# USB_CY7C68001-56LFC.net
KiCad netlist of a schematic drawn in Altium Designer
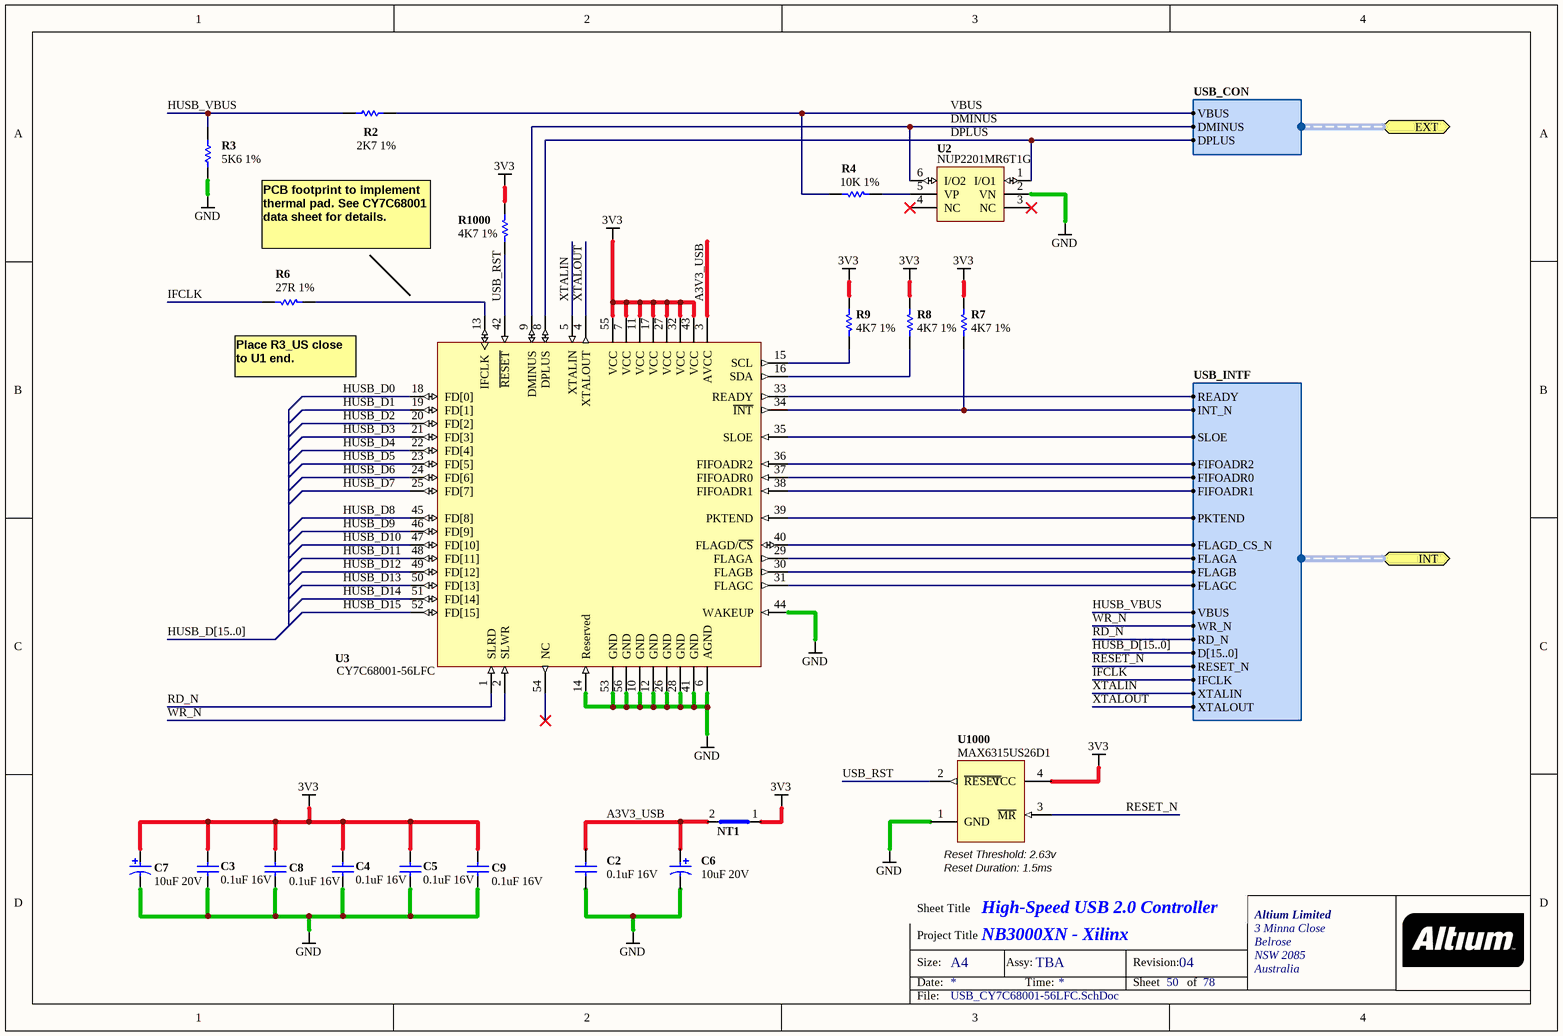
[diagram p0: USB_CY7C68001-56LFC.SchDoc]

(export (version "E")
  (design (tool "Eeschema 10.0.6"))
  (components
    (comp (ref "C2")
      (value "0.1uF 16V")
      (footprint "CAPC1005-STAR")
      (description "Capacitor, Ceramic, 0.1uF 10% 16V 0402 (1005) X7R")
      (fields (field (name "TOLERANCE") "10 %"))
      (libsource (lib "AltiumDesignLibrary") (part "CAP-NP"))
    )
    (comp (ref "C3")
      (value "0.1uF 16V")
      (footprint "CAPC1005-STAR")
      (description "Capacitor, Ceramic, 0.1uF 10% 16V 0402 (1005) X7R")
      (fields (field (name "TOLERANCE") "10 %"))
      (libsource (lib "AltiumDesignLibrary") (part "CAP-NP"))
    )
    (comp (ref "C4")
      (value "0.1uF 16V")
      (footprint "CAPC1005-STAR")
      (description "Capacitor, Ceramic, 0.1uF 10% 16V 0402 (1005) X7R")
      (fields (field (name "TOLERANCE") "10 %"))
      (libsource (lib "AltiumDesignLibrary") (part "CAP-NP"))
    )
    (comp (ref "C5")
      (value "0.1uF 16V")
      (footprint "CAPC1005-STAR")
      (description "Capacitor, Ceramic, 0.1uF 10% 16V 0402 (1005) X7R")
      (fields (field (name "TOLERANCE") "10 %"))
      (libsource (lib "AltiumDesignLibrary") (part "CAP-NP"))
    )
    (comp (ref "C6")
      (value "10uF 20V")
      (footprint "CAPC3528-STAR")
      (description "Capacitor, Tantalum, 10uF 10% 20V MCCT-B (3528)")
      (fields (field (name "TOLERANCE") "10 %"))
      (libsource (lib "") (part "CAP-P_1"))
    )
    (comp (ref "C7")
      (value "10uF 20V")
      (footprint "CAPC3528-STAR")
      (description "Capacitor, Tantalum, 10uF 10% 20V MCCT-B (3528)")
      (fields (field (name "TOLERANCE") "10 %"))
      (libsource (lib "AltiumDesignLibrary") (part "CAP-P"))
    )
    (comp (ref "C8")
      (value "0.1uF 16V")
      (footprint "CAPC1005-STAR")
      (description "Capacitor, Ceramic, 0.1uF 10% 16V 0402 (1005) X7R")
      (fields (field (name "TOLERANCE") "10 %"))
      (libsource (lib "AltiumDesignLibrary") (part "CAP-NP"))
    )
    (comp (ref "C9")
      (value "0.1uF 16V")
      (footprint "CAPC1005-STAR")
      (description "Capacitor, Ceramic, 0.1uF 10% 16V 0402 (1005) X7R")
      (fields (field (name "TOLERANCE") "10 %"))
      (libsource (lib "AltiumDesignLibrary") (part "CAP-NP"))
    )
    (comp (ref "NT1")
      (value "Net Tie SMT2")
      (footprint "NETTIE-SMT2-31X51")
      (description "Net-Tie, Surface Mount, 2 x 1.6mm x 0.8mm SMT Pads - For 0.8mm Track")
      (libsource (lib "AltiumDesignLibrary") (part "NETTIE-SMT2"))
    )
    (comp (ref "R2")
      (value "2K7 1%")
      (footprint "RESC1005-STAR")
      (description "Resistor, 2K7 1% 0402 (1005)")
      (fields (field (name "TOLERANCE") "1 %"))
      (libsource (lib "AltiumDesignLibrary") (part "RES"))
    )
    (comp (ref "R3")
      (value "5K6 1%")
      (footprint "RESC1005-STAR")
      (description "Resistor, 5K6 1% 0402 (1005)")
      (fields (field (name "TOLERANCE") "1 %"))
      (libsource (lib "AltiumDesignLibrary") (part "RES"))
    )
    (comp (ref "R4")
      (value "10K 1%")
      (footprint "RESC1005-STAR")
      (description "Resistor, 10K 1% 0402 (1005)")
      (fields (field (name "TOLERANCE") "1 %"))
      (libsource (lib "AltiumDesignLibrary") (part "RES"))
    )
    (comp (ref "R6")
      (value "27R 1%")
      (footprint "RESC1005-STAR")
      (description "Resistor, 27R 1% 0402 (1005)")
      (fields (field (name "TOLERANCE") "1 %"))
      (libsource (lib "AltiumDesignLibrary") (part "RES"))
    )
    (comp (ref "R7")
      (value "4K7 1%")
      (footprint "RESC1005-STAR")
      (description "Resistor, 4K7 1% 0402 (1005)")
      (fields (field (name "TOLERANCE") "1 %"))
      (libsource (lib "AltiumDesignLibrary") (part "RES"))
    )
    (comp (ref "R8")
      (value "4K7 1%")
      (footprint "RESC1005-STAR")
      (description "Resistor, 4K7 1% 0402 (1005)")
      (fields (field (name "TOLERANCE") "1 %"))
      (libsource (lib "AltiumDesignLibrary") (part "RES"))
    )
    (comp (ref "R9")
      (value "4K7 1%")
      (footprint "RESC1005-STAR")
      (description "Resistor, 4K7 1% 0402 (1005)")
      (fields (field (name "TOLERANCE") "1 %"))
      (libsource (lib "AltiumDesignLibrary") (part "RES"))
    )
    (comp (ref "R1000")
      (value "4K7 1%")
      (footprint "RESC1005-STAR")
      (description "Resistor, 4K7 1% 0402 (1005)")
      (fields (field (name "TOLERANCE") "1 %"))
      (libsource (lib "AltiumDesignLibrary") (part "RES"))
    )
    (comp (ref "U2")
      (value "NUP2201MR6T1G")
      (footprint "TSOP95P275-6")
      (description "NUP2201MR6, Low Capacitance Diode Array, USB Protection")
      (libsource (lib "AltiumDesignLibrary") (part "NUP2201MR6"))
    )
    (comp (ref "U3")
      (value "CY7C68001-56LFC")
      (footprint "QFN50P800X800_HS-57")
      (description "CY7C68001-56LFC, EZ-USB SX2 High-Speed USB Interface")
      (libsource (lib "AltiumDesignLibrary") (part "CY7C68001-56LFC"))
    )
    (comp (ref "U1000")
      (value "MAX6315US26D1")
      (footprint "SOT143")
      (description "MAX6315, Open-Drain Output SOT Reset IC, Customized Reset Thresholds, Timeout Delays")
      (libsource (lib "AltiumDesignLibrary") (part "MAX6315"))
    )
  )
  (nets
    (net (code "3") (name "/A3V3_USB") (class "Default")
      (node (ref "C2") (pin "2") (pinfunction "2_2") (pintype "passive"))
      (node (ref "C6") (pin "1") (pinfunction "1_1") (pintype "passive"))
      (node (ref "NT1") (pin "2") (pinfunction "Net2_2") (pintype "passive"))
      (node (ref "U3") (pin "3") (pinfunction "AVCC_3") (pintype "power_in"))
    )
    (net (code "4") (name "/DMINUS") (class "Default")
      (node (ref "U2") (pin "6") (pinfunction "I/O2_6") (pintype "bidirectional"))
      (node (ref "U3") (pin "9") (pinfunction "DMINUS_9") (pintype "bidirectional"))
    )
    (net (code "5") (name "/DPLUS") (class "Default")
      (node (ref "U2") (pin "1") (pinfunction "I/O1_1") (pintype "bidirectional"))
      (node (ref "U3") (pin "8") (pinfunction "DPLUS_8") (pintype "bidirectional"))
    )
    (net (code "6") (name "/FIFOADR0") (class "Default")
      (node (ref "U3") (pin "37") (pinfunction "FIFOADR0_37") (pintype "input"))
    )
    (net (code "7") (name "/FIFOADR1") (class "Default")
      (node (ref "U3") (pin "38") (pinfunction "FIFOADR1_38") (pintype "input"))
    )
    (net (code "8") (name "/FIFOADR2") (class "Default")
      (node (ref "U3") (pin "36") (pinfunction "FIFOADR2_36") (pintype "input"))
    )
    (net (code "9") (name "/FLAGA") (class "Default")
      (node (ref "U3") (pin "29") (pinfunction "FLAGA_29") (pintype "output"))
    )
    (net (code "10") (name "/FLAGB") (class "Default")
      (node (ref "U3") (pin "30") (pinfunction "FLAGB_30") (pintype "output"))
    )
    (net (code "11") (name "/FLAGC") (class "Default")
      (node (ref "U3") (pin "31") (pinfunction "FLAGC_31") (pintype "output"))
    )
    (net (code "12") (name "/FLAGD_CS_N") (class "Default")
      (node (ref "U3") (pin "40") (pinfunction "FLAGD/~{CS}_40") (pintype "bidirectional"))
    )
    (net (code "13") (name "/HUSB_D0") (class "Default")
      (node (ref "U3") (pin "18") (pinfunction "FD[0]_18") (pintype "bidirectional"))
    )
    (net (code "14") (name "/HUSB_D1") (class "Default")
      (node (ref "U3") (pin "19") (pinfunction "FD[1]_19") (pintype "bidirectional"))
    )
    (net (code "15") (name "/HUSB_D2") (class "Default")
      (node (ref "U3") (pin "20") (pinfunction "FD[2]_20") (pintype "bidirectional"))
    )
    (net (code "16") (name "/HUSB_D3") (class "Default")
      (node (ref "U3") (pin "21") (pinfunction "FD[3]_21") (pintype "bidirectional"))
    )
    (net (code "17") (name "/HUSB_D4") (class "Default")
      (node (ref "U3") (pin "22") (pinfunction "FD[4]_22") (pintype "bidirectional"))
    )
    (net (code "18") (name "/HUSB_D5") (class "Default")
      (node (ref "U3") (pin "23") (pinfunction "FD[5]_23") (pintype "bidirectional"))
    )
    (net (code "19") (name "/HUSB_D6") (class "Default")
      (node (ref "U3") (pin "24") (pinfunction "FD[6]_24") (pintype "bidirectional"))
    )
    (net (code "20") (name "/HUSB_D7") (class "Default")
      (node (ref "U3") (pin "25") (pinfunction "FD[7]_25") (pintype "bidirectional"))
    )
    (net (code "21") (name "/HUSB_D8") (class "Default")
      (node (ref "U3") (pin "45") (pinfunction "FD[8]_45") (pintype "bidirectional"))
    )
    (net (code "22") (name "/HUSB_D9") (class "Default")
      (node (ref "U3") (pin "46") (pinfunction "FD[9]_46") (pintype "bidirectional"))
    )
    (net (code "23") (name "/HUSB_D10") (class "Default")
      (node (ref "U3") (pin "47") (pinfunction "FD[10]_47") (pintype "bidirectional"))
    )
    (net (code "24") (name "/HUSB_D11") (class "Default")
      (node (ref "U3") (pin "48") (pinfunction "FD[11]_48") (pintype "bidirectional"))
    )
    (net (code "25") (name "/HUSB_D12") (class "Default")
      (node (ref "U3") (pin "49") (pinfunction "FD[12]_49") (pintype "bidirectional"))
    )
    (net (code "26") (name "/HUSB_D13") (class "Default")
      (node (ref "U3") (pin "50") (pinfunction "FD[13]_50") (pintype "bidirectional"))
    )
    (net (code "27") (name "/HUSB_D14") (class "Default")
      (node (ref "U3") (pin "51") (pinfunction "FD[14]_51") (pintype "bidirectional"))
    )
    (net (code "28") (name "/HUSB_D15") (class "Default")
      (node (ref "U3") (pin "52") (pinfunction "FD[15]_52") (pintype "bidirectional"))
    )
    (net (code "30") (name "/HUSB_VBUS") (class "Default")
      (node (ref "R2") (pin "1") (pinfunction "1_1") (pintype "passive"))
      (node (ref "R3") (pin "1") (pinfunction "1_1") (pintype "passive"))
    )
    (net (code "31") (name "/IFCLK") (class "Default")
      (node (ref "R6") (pin "1") (pinfunction "1_1") (pintype "passive"))
    )
    (net (code "32") (name "/INT_N") (class "Default")
      (node (ref "R7") (pin "1") (pinfunction "1_1") (pintype "passive"))
      (node (ref "U3") (pin "34") (pinfunction "~{INT}_34") (pintype "output"))
    )
    (net (code "34") (name "/PKTEND") (class "Default")
      (node (ref "U3") (pin "39") (pinfunction "PKTEND_39") (pintype "input"))
    )
    (net (code "35") (name "/RD_N") (class "Default")
      (node (ref "U3") (pin "1") (pinfunction "SLRD_1") (pintype "input"))
    )
    (net (code "36") (name "/READY") (class "Default")
      (node (ref "U3") (pin "33") (pinfunction "READY_33") (pintype "output"))
    )
    (net (code "37") (name "/RESET_N") (class "Default")
      (node (ref "U1000") (pin "3") (pinfunction "~{MR}_3") (pintype "input"))
    )
    (net (code "38") (name "/SLOE") (class "Default")
      (node (ref "U3") (pin "35") (pinfunction "SLOE_35") (pintype "input"))
    )
    (net (code "39") (name "/USB_RST") (class "Default")
      (node (ref "R1000") (pin "1") (pinfunction "1_1") (pintype "passive"))
      (node (ref "U1000") (pin "2") (pinfunction "~{RESET}_2") (pintype "output"))
      (node (ref "U3") (pin "42") (pinfunction "~{RESET}_42") (pintype "input"))
    )
    (net (code "40") (name "/VBUS") (class "Default")
      (node (ref "R2") (pin "2") (pinfunction "2_2") (pintype "passive"))
      (node (ref "R4") (pin "1") (pinfunction "1_1") (pintype "passive"))
    )
    (net (code "41") (name "/WR_N") (class "Default")
      (node (ref "U3") (pin "2") (pinfunction "SLWR_2") (pintype "input"))
    )
    (net (code "42") (name "/XTALIN") (class "Default")
      (node (ref "U3") (pin "5") (pinfunction "XTALIN_5") (pintype "input"))
    )
    (net (code "43") (name "/XTALOUT") (class "Default")
      (node (ref "U3") (pin "4") (pinfunction "XTALOUT_4") (pintype "output"))
    )
    (net (code "46") (name "3V3") (class "Default")
      (node (ref "C3") (pin "2") (pinfunction "2_2") (pintype "passive"))
      (node (ref "C4") (pin "2") (pinfunction "2_2") (pintype "passive"))
      (node (ref "C5") (pin "2") (pinfunction "2_2") (pintype "passive"))
      (node (ref "C7") (pin "1") (pinfunction "1_1") (pintype "passive"))
      (node (ref "C8") (pin "1") (pinfunction "1_1") (pintype "passive"))
      (node (ref "C9") (pin "1") (pinfunction "1_1") (pintype "passive"))
      (node (ref "NT1") (pin "1") (pinfunction "Net1_1") (pintype "passive"))
      (node (ref "R1000") (pin "2") (pinfunction "2_2") (pintype "passive"))
      (node (ref "R7") (pin "2") (pinfunction "2_2") (pintype "passive"))
      (node (ref "R8") (pin "1") (pinfunction "1_1") (pintype "passive"))
      (node (ref "R9") (pin "1") (pinfunction "1_1") (pintype "passive"))
      (node (ref "U1000") (pin "4") (pinfunction "VCC_4") (pintype "power_in"))
      (node (ref "U3") (pin "11") (pinfunction "VCC_11") (pintype "power_in"))
      (node (ref "U3") (pin "17") (pinfunction "VCC_17") (pintype "power_in"))
      (node (ref "U3") (pin "27") (pinfunction "VCC_27") (pintype "power_in"))
      (node (ref "U3") (pin "32") (pinfunction "VCC_32") (pintype "power_in"))
      (node (ref "U3") (pin "43") (pinfunction "VCC_43") (pintype "power_in"))
      (node (ref "U3") (pin "55") (pinfunction "VCC_55") (pintype "power_in"))
      (node (ref "U3") (pin "7") (pinfunction "VCC_7") (pintype "power_in"))
    )
    (net (code "47") (name "GND") (class "Default")
      (node (ref "C2") (pin "1") (pinfunction "1_1") (pintype "passive"))
      (node (ref "C3") (pin "1") (pinfunction "1_1") (pintype "passive"))
      (node (ref "C4") (pin "1") (pinfunction "1_1") (pintype "passive"))
      (node (ref "C5") (pin "1") (pinfunction "1_1") (pintype "passive"))
      (node (ref "C6") (pin "2") (pinfunction "2_2") (pintype "passive"))
      (node (ref "C7") (pin "2") (pinfunction "2_2") (pintype "passive"))
      (node (ref "C8") (pin "2") (pinfunction "2_2") (pintype "passive"))
      (node (ref "C9") (pin "2") (pinfunction "2_2") (pintype "passive"))
      (node (ref "R3") (pin "2") (pinfunction "2_2") (pintype "passive"))
      (node (ref "U1000") (pin "1") (pinfunction "GND_1") (pintype "power_in"))
      (node (ref "U2") (pin "2") (pinfunction "VN_2") (pintype "power_in"))
      (node (ref "U3") (pin "10") (pinfunction "GND_10") (pintype "power_in"))
      (node (ref "U3") (pin "12") (pinfunction "GND_12") (pintype "power_in"))
      (node (ref "U3") (pin "14") (pinfunction "Reserved_14") (pintype "input"))
      (node (ref "U3") (pin "26") (pinfunction "GND_26") (pintype "power_in"))
      (node (ref "U3") (pin "28") (pinfunction "GND_28") (pintype "power_in"))
      (node (ref "U3") (pin "41") (pinfunction "GND_41") (pintype "power_in"))
      (node (ref "U3") (pin "44") (pinfunction "WAKEUP_44") (pintype "input"))
      (node (ref "U3") (pin "53") (pinfunction "GND_53") (pintype "power_in"))
      (node (ref "U3") (pin "56") (pinfunction "GND_56") (pintype "power_in"))
      (node (ref "U3") (pin "6") (pinfunction "AGND_6") (pintype "power_in"))
    )
    (net (code "48") (name "Net-(U2-VP)") (class "Default")
      (node (ref "R4") (pin "2") (pinfunction "2_2") (pintype "passive"))
      (node (ref "U2") (pin "5") (pinfunction "VP_5") (pintype "power_in"))
    )
    (net (code "49") (name "Net-(U3-IFCLK)") (class "Default")
      (node (ref "R6") (pin "2") (pinfunction "2_2") (pintype "passive"))
      (node (ref "U3") (pin "13") (pinfunction "IFCLK_13") (pintype "bidirectional"))
    )
    (net (code "50") (name "Net-(U3-SCL)") (class "Default")
      (node (ref "R9") (pin "2") (pinfunction "2_2") (pintype "passive"))
      (node (ref "U3") (pin "15") (pinfunction "SCL_15") (pintype "output"))
    )
    (net (code "51") (name "Net-(U3-SDA)") (class "Default")
      (node (ref "R8") (pin "2") (pinfunction "2_2") (pintype "passive"))
      (node (ref "U3") (pin "16") (pinfunction "SDA_16") (pintype "output"))
    )
    (net (code "52") (name "unconnected-(U2-NC-Pad3)") (class "Default")
      (node (ref "U2") (pin "3") (pinfunction "NC_3") (pintype "passive+no_connect"))
    )
    (net (code "53") (name "unconnected-(U2-NC-Pad4)") (class "Default")
      (node (ref "U2") (pin "4") (pinfunction "NC_4") (pintype "passive+no_connect"))
    )
    (net (code "54") (name "unconnected-(U3-NC-Pad54)") (class "Default")
      (node (ref "U3") (pin "54") (pinfunction "NC_54") (pintype "output+no_connect"))
    )
  )
)
